# I2CBB-R1.net
KiCad netlist of a schematic drawn in EAGLE
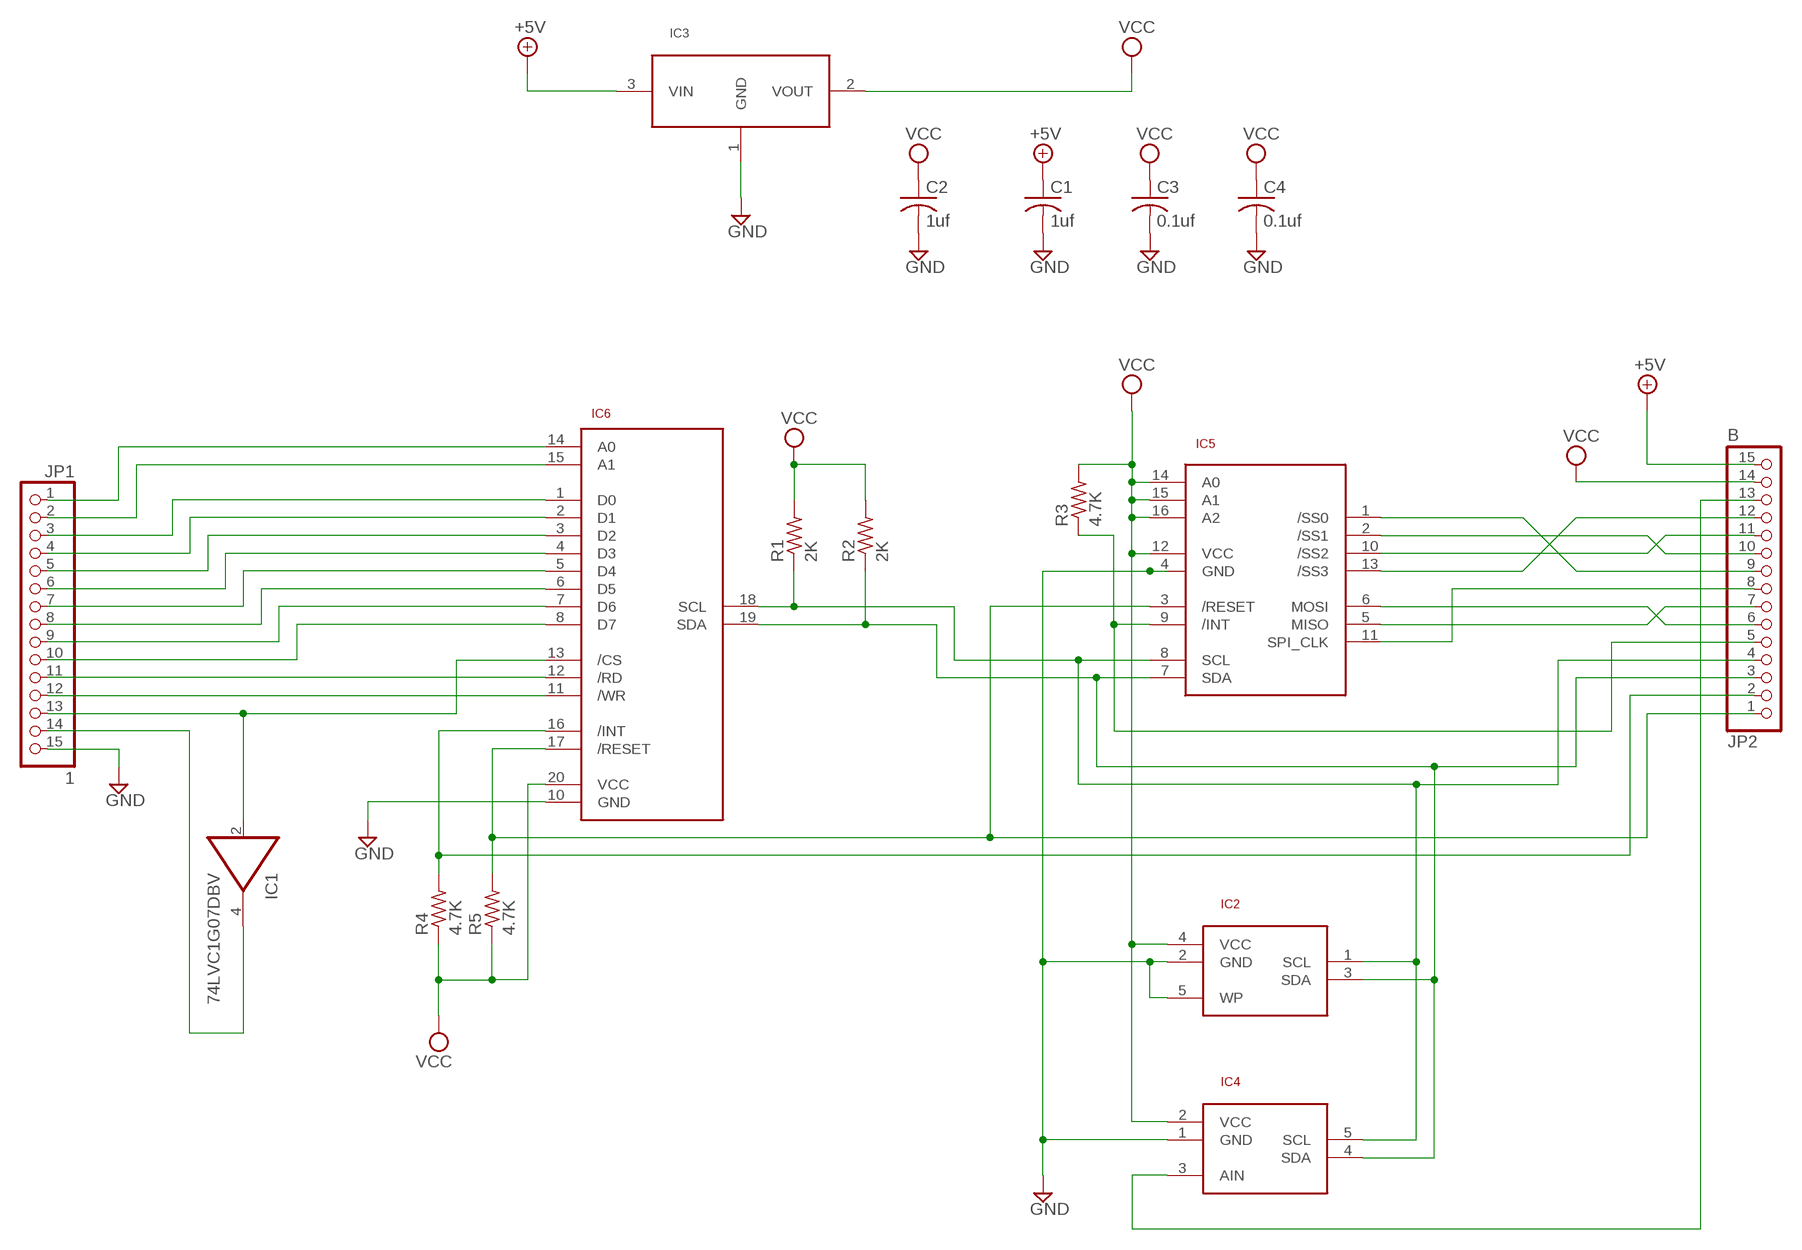
[diagram p0: schematic, sheet 1]

(export (version "E")
  (design (tool "Eeschema 10.0.6"))
  (components
    (comp (ref "C1")
      (value "1uf")
      (footprint "eagle-import:C0603")
      (libsource (lib "eagle-import") (part "C-USC0603"))
    )
    (comp (ref "C2")
      (value "1uf")
      (footprint "eagle-import:C0603")
      (libsource (lib "eagle-import") (part "C-USC0603"))
    )
    (comp (ref "C3")
      (value "0.1uf")
      (footprint "eagle-import:C0603")
      (libsource (lib "eagle-import") (part "C-USC0603"))
    )
    (comp (ref "C4")
      (value "0.1uf")
      (footprint "eagle-import:C0603")
      (libsource (lib "eagle-import") (part "C-USC0603"))
    )
    (comp (ref "IC1")
      (value "74LVC1G07DBV")
      (footprint "eagle-import:SOT23-5")
      (libsource (lib "eagle-import") (part "741G07DBVLVC"))
    )
    (comp (ref "IC2")
      (value "24AA64T")
      (footprint "eagle-import:SOT23-5")
      (libsource (lib "eagle-import") (part "24AA64T"))
    )
    (comp (ref "IC3")
      (value "MCP1700T")
      (footprint "eagle-import:SOT23")
      (libsource (lib "eagle-import") (part "MCP1700T"))
    )
    (comp (ref "IC4")
      (value "MCP3221")
      (footprint "eagle-import:SOT23-5")
      (libsource (lib "eagle-import") (part "MCP3221"))
    )
    (comp (ref "IC5")
      (value "SC18IS602")
      (footprint "eagle-import:TSSOP16")
      (libsource (lib "eagle-import") (part "SC18IS602"))
    )
    (comp (ref "IC6")
      (value "PCA9665")
      (footprint "eagle-import:TSSOP20")
      (libsource (lib "eagle-import") (part "PCA9665"))
    )
    (comp (ref "JP1")
      (value "1")
      (footprint "eagle-import:1X15")
      (libsource (lib "eagle-import") (part "PINHD-1X15"))
    )
    (comp (ref "JP2")
      (value "B")
      (footprint "eagle-import:1X15")
      (libsource (lib "eagle-import") (part "PINHD-1X15"))
    )
    (comp (ref "R1")
      (value "2K")
      (footprint "eagle-import:R0603")
      (libsource (lib "eagle-import") (part "R-US_R0603"))
    )
    (comp (ref "R2")
      (value "2K")
      (footprint "eagle-import:R0603")
      (libsource (lib "eagle-import") (part "R-US_R0603"))
    )
    (comp (ref "R3")
      (value "4.7K")
      (footprint "eagle-import:R0603")
      (libsource (lib "eagle-import") (part "R-US_R0603"))
    )
    (comp (ref "R4")
      (value "4.7K")
      (footprint "eagle-import:R0603")
      (libsource (lib "eagle-import") (part "R-US_R0603"))
    )
    (comp (ref "R5")
      (value "4.7K")
      (footprint "eagle-import:R0603")
      (libsource (lib "eagle-import") (part "R-US_R0603"))
    )
  )
  (nets
    (net (code "1") (name "+5V") (class "Default")
      (node (ref "C1") (pin "1") (pinfunction "1_1") (pintype "passive"))
      (node (ref "IC3") (pin "3") (pinfunction "VIN_3") (pintype "power_in"))
      (node (ref "JP2") (pin "15") (pinfunction "15_15") (pintype "passive"))
    )
    (net (code "2") (name "GND") (class "Default")
      (node (ref "C1") (pin "2") (pinfunction "2_2") (pintype "passive"))
      (node (ref "C2") (pin "2") (pinfunction "2_2") (pintype "passive"))
      (node (ref "C3") (pin "2") (pinfunction "2_2") (pintype "passive"))
      (node (ref "C4") (pin "2") (pinfunction "2_2") (pintype "passive"))
      (node (ref "IC2") (pin "2") (pinfunction "GND_2") (pintype "bidirectional"))
      (node (ref "IC2") (pin "5") (pinfunction "WP_5") (pintype "bidirectional"))
      (node (ref "IC3") (pin "1") (pinfunction "GND_1") (pintype "power_in"))
      (node (ref "IC4") (pin "1") (pinfunction "GND_1") (pintype "power_in"))
      (node (ref "IC5") (pin "4") (pinfunction "GND_4") (pintype "power_in"))
      (node (ref "IC6") (pin "10") (pinfunction "GND_10") (pintype "power_in"))
      (node (ref "JP1") (pin "15") (pinfunction "15_15") (pintype "passive"))
    )
    (net (code "3") (name "Net-(IC1A-I)") (class "Default")
      (node (ref "IC1") (pin "2") (pinfunction "I_2") (pintype "input"))
      (node (ref "IC6") (pin "13") (pinfunction "/CS_13") (pintype "input"))
      (node (ref "JP1") (pin "13") (pinfunction "13_13") (pintype "passive"))
    )
    (net (code "4") (name "Net-(IC1A-O)") (class "Default")
      (node (ref "IC1") (pin "4") (pinfunction "O_4") (pintype "open_collector"))
      (node (ref "JP1") (pin "14") (pinfunction "14_14") (pintype "passive"))
    )
    (net (code "5") (name "Net-(IC2-SCL)") (class "Default")
      (node (ref "IC2") (pin "1") (pinfunction "SCL_1") (pintype "bidirectional"))
      (node (ref "IC4") (pin "5") (pinfunction "SCL_5") (pintype "bidirectional"))
      (node (ref "IC5") (pin "8") (pinfunction "SCL_8") (pintype "bidirectional"))
      (node (ref "IC6") (pin "18") (pinfunction "SCL_18") (pintype "bidirectional"))
      (node (ref "JP2") (pin "4") (pinfunction "4_4") (pintype "passive"))
      (node (ref "R1") (pin "1") (pinfunction "1_1") (pintype "passive"))
    )
    (net (code "6") (name "Net-(IC2-SDA)") (class "Default")
      (node (ref "IC2") (pin "3") (pinfunction "SDA_3") (pintype "bidirectional"))
      (node (ref "IC4") (pin "4") (pinfunction "SDA_4") (pintype "bidirectional"))
      (node (ref "IC5") (pin "7") (pinfunction "SDA_7") (pintype "bidirectional"))
      (node (ref "IC6") (pin "19") (pinfunction "SDA_19") (pintype "bidirectional"))
      (node (ref "JP2") (pin "3") (pinfunction "3_3") (pintype "passive"))
      (node (ref "R2") (pin "1") (pinfunction "1_1") (pintype "passive"))
    )
    (net (code "7") (name "Net-(IC4-AIN)") (class "Default")
      (node (ref "IC4") (pin "3") (pinfunction "AIN_3") (pintype "input"))
      (node (ref "JP2") (pin "13") (pinfunction "13_13") (pintype "passive"))
    )
    (net (code "8") (name "Net-(IC5-MISO)") (class "Default")
      (node (ref "IC5") (pin "5") (pinfunction "MISO_5") (pintype "bidirectional"))
      (node (ref "JP2") (pin "7") (pinfunction "7_7") (pintype "passive"))
    )
    (net (code "9") (name "Net-(IC5-MOSI)") (class "Default")
      (node (ref "IC5") (pin "6") (pinfunction "MOSI_6") (pintype "bidirectional"))
      (node (ref "JP2") (pin "6") (pinfunction "6_6") (pintype "passive"))
    )
    (net (code "10") (name "Net-(IC5-SPI_CLK)") (class "Default")
      (node (ref "IC5") (pin "11") (pinfunction "SPI_CLK_11") (pintype "bidirectional"))
      (node (ref "JP2") (pin "8") (pinfunction "8_8") (pintype "passive"))
    )
    (net (code "11") (name "Net-(IC5-{slash}INT)") (class "Default")
      (node (ref "IC5") (pin "9") (pinfunction "/INT_9") (pintype "output"))
      (node (ref "JP2") (pin "5") (pinfunction "5_5") (pintype "passive"))
      (node (ref "R3") (pin "1") (pinfunction "1_1") (pintype "passive"))
    )
    (net (code "12") (name "Net-(IC5-{slash}RESET)") (class "Default")
      (node (ref "IC5") (pin "3") (pinfunction "/RESET_3") (pintype "input"))
      (node (ref "IC6") (pin "17") (pinfunction "/RESET_17") (pintype "input"))
      (node (ref "JP2") (pin "1") (pinfunction "1_1") (pintype "passive"))
      (node (ref "R5") (pin "2") (pinfunction "2_2") (pintype "passive"))
    )
    (net (code "13") (name "Net-(IC5-{slash}SS0)") (class "Default")
      (node (ref "IC5") (pin "1") (pinfunction "/SS0_1") (pintype "bidirectional"))
      (node (ref "JP2") (pin "9") (pinfunction "9_9") (pintype "passive"))
    )
    (net (code "14") (name "Net-(IC5-{slash}SS1)") (class "Default")
      (node (ref "IC5") (pin "2") (pinfunction "/SS1_2") (pintype "bidirectional"))
      (node (ref "JP2") (pin "10") (pinfunction "10_10") (pintype "passive"))
    )
    (net (code "15") (name "Net-(IC5-{slash}SS2)") (class "Default")
      (node (ref "IC5") (pin "10") (pinfunction "/SS2_10") (pintype "bidirectional"))
      (node (ref "JP2") (pin "11") (pinfunction "11_11") (pintype "passive"))
    )
    (net (code "16") (name "Net-(IC5-{slash}SS3)") (class "Default")
      (node (ref "IC5") (pin "13") (pinfunction "/SS3_13") (pintype "bidirectional"))
      (node (ref "JP2") (pin "12") (pinfunction "12_12") (pintype "passive"))
    )
    (net (code "17") (name "Net-(IC6-A0)") (class "Default")
      (node (ref "IC6") (pin "14") (pinfunction "A0_14") (pintype "input"))
      (node (ref "JP1") (pin "1") (pinfunction "1_1") (pintype "passive"))
    )
    (net (code "18") (name "Net-(IC6-A1)") (class "Default")
      (node (ref "IC6") (pin "15") (pinfunction "A1_15") (pintype "input"))
      (node (ref "JP1") (pin "2") (pinfunction "2_2") (pintype "passive"))
    )
    (net (code "19") (name "Net-(IC6-D0)") (class "Default")
      (node (ref "IC6") (pin "1") (pinfunction "D0_1") (pintype "bidirectional"))
      (node (ref "JP1") (pin "3") (pinfunction "3_3") (pintype "passive"))
    )
    (net (code "20") (name "Net-(IC6-D1)") (class "Default")
      (node (ref "IC6") (pin "2") (pinfunction "D1_2") (pintype "bidirectional"))
      (node (ref "JP1") (pin "4") (pinfunction "4_4") (pintype "passive"))
    )
    (net (code "21") (name "Net-(IC6-D2)") (class "Default")
      (node (ref "IC6") (pin "3") (pinfunction "D2_3") (pintype "bidirectional"))
      (node (ref "JP1") (pin "5") (pinfunction "5_5") (pintype "passive"))
    )
    (net (code "22") (name "Net-(IC6-D3)") (class "Default")
      (node (ref "IC6") (pin "4") (pinfunction "D3_4") (pintype "bidirectional"))
      (node (ref "JP1") (pin "6") (pinfunction "6_6") (pintype "passive"))
    )
    (net (code "23") (name "Net-(IC6-D4)") (class "Default")
      (node (ref "IC6") (pin "5") (pinfunction "D4_5") (pintype "bidirectional"))
      (node (ref "JP1") (pin "7") (pinfunction "7_7") (pintype "passive"))
    )
    (net (code "24") (name "Net-(IC6-D5)") (class "Default")
      (node (ref "IC6") (pin "6") (pinfunction "D5_6") (pintype "bidirectional"))
      (node (ref "JP1") (pin "8") (pinfunction "8_8") (pintype "passive"))
    )
    (net (code "25") (name "Net-(IC6-D6)") (class "Default")
      (node (ref "IC6") (pin "7") (pinfunction "D6_7") (pintype "bidirectional"))
      (node (ref "JP1") (pin "9") (pinfunction "9_9") (pintype "passive"))
    )
    (net (code "26") (name "Net-(IC6-D7)") (class "Default")
      (node (ref "IC6") (pin "8") (pinfunction "D7_8") (pintype "bidirectional"))
      (node (ref "JP1") (pin "10") (pinfunction "10_10") (pintype "passive"))
    )
    (net (code "27") (name "Net-(IC6-{slash}INT)") (class "Default")
      (node (ref "IC6") (pin "16") (pinfunction "/INT_16") (pintype "input"))
      (node (ref "JP2") (pin "2") (pinfunction "2_2") (pintype "passive"))
      (node (ref "R4") (pin "2") (pinfunction "2_2") (pintype "passive"))
    )
    (net (code "28") (name "Net-(IC6-{slash}RD)") (class "Default")
      (node (ref "IC6") (pin "12") (pinfunction "/RD_12") (pintype "input"))
      (node (ref "JP1") (pin "11") (pinfunction "11_11") (pintype "passive"))
    )
    (net (code "29") (name "Net-(IC6-{slash}WR)") (class "Default")
      (node (ref "IC6") (pin "11") (pinfunction "/WR_11") (pintype "input"))
      (node (ref "JP1") (pin "12") (pinfunction "12_12") (pintype "passive"))
    )
    (net (code "30") (name "VCC") (class "Default")
      (node (ref "C2") (pin "1") (pinfunction "1_1") (pintype "passive"))
      (node (ref "C3") (pin "1") (pinfunction "1_1") (pintype "passive"))
      (node (ref "C4") (pin "1") (pinfunction "1_1") (pintype "passive"))
      (node (ref "IC2") (pin "4") (pinfunction "VCC_4") (pintype "bidirectional"))
      (node (ref "IC3") (pin "2") (pinfunction "VOUT_2") (pintype "power_in"))
      (node (ref "IC4") (pin "2") (pinfunction "VCC_2") (pintype "power_in"))
      (node (ref "IC5") (pin "12") (pinfunction "VCC_12") (pintype "power_in"))
      (node (ref "IC5") (pin "14") (pinfunction "A0_14") (pintype "bidirectional"))
      (node (ref "IC5") (pin "15") (pinfunction "A1_15") (pintype "bidirectional"))
      (node (ref "IC5") (pin "16") (pinfunction "A2_16") (pintype "bidirectional"))
      (node (ref "IC6") (pin "20") (pinfunction "VCC_20") (pintype "power_in"))
      (node (ref "JP2") (pin "14") (pinfunction "14_14") (pintype "passive"))
      (node (ref "R1") (pin "2") (pinfunction "2_2") (pintype "passive"))
      (node (ref "R2") (pin "2") (pinfunction "2_2") (pintype "passive"))
      (node (ref "R3") (pin "2") (pinfunction "2_2") (pintype "passive"))
      (node (ref "R4") (pin "1") (pinfunction "1_1") (pintype "passive"))
      (node (ref "R5") (pin "1") (pinfunction "1_1") (pintype "passive"))
    )
  )
)
